# schematic.net
KiCad netlist of a schematic drawn in EasyEDA
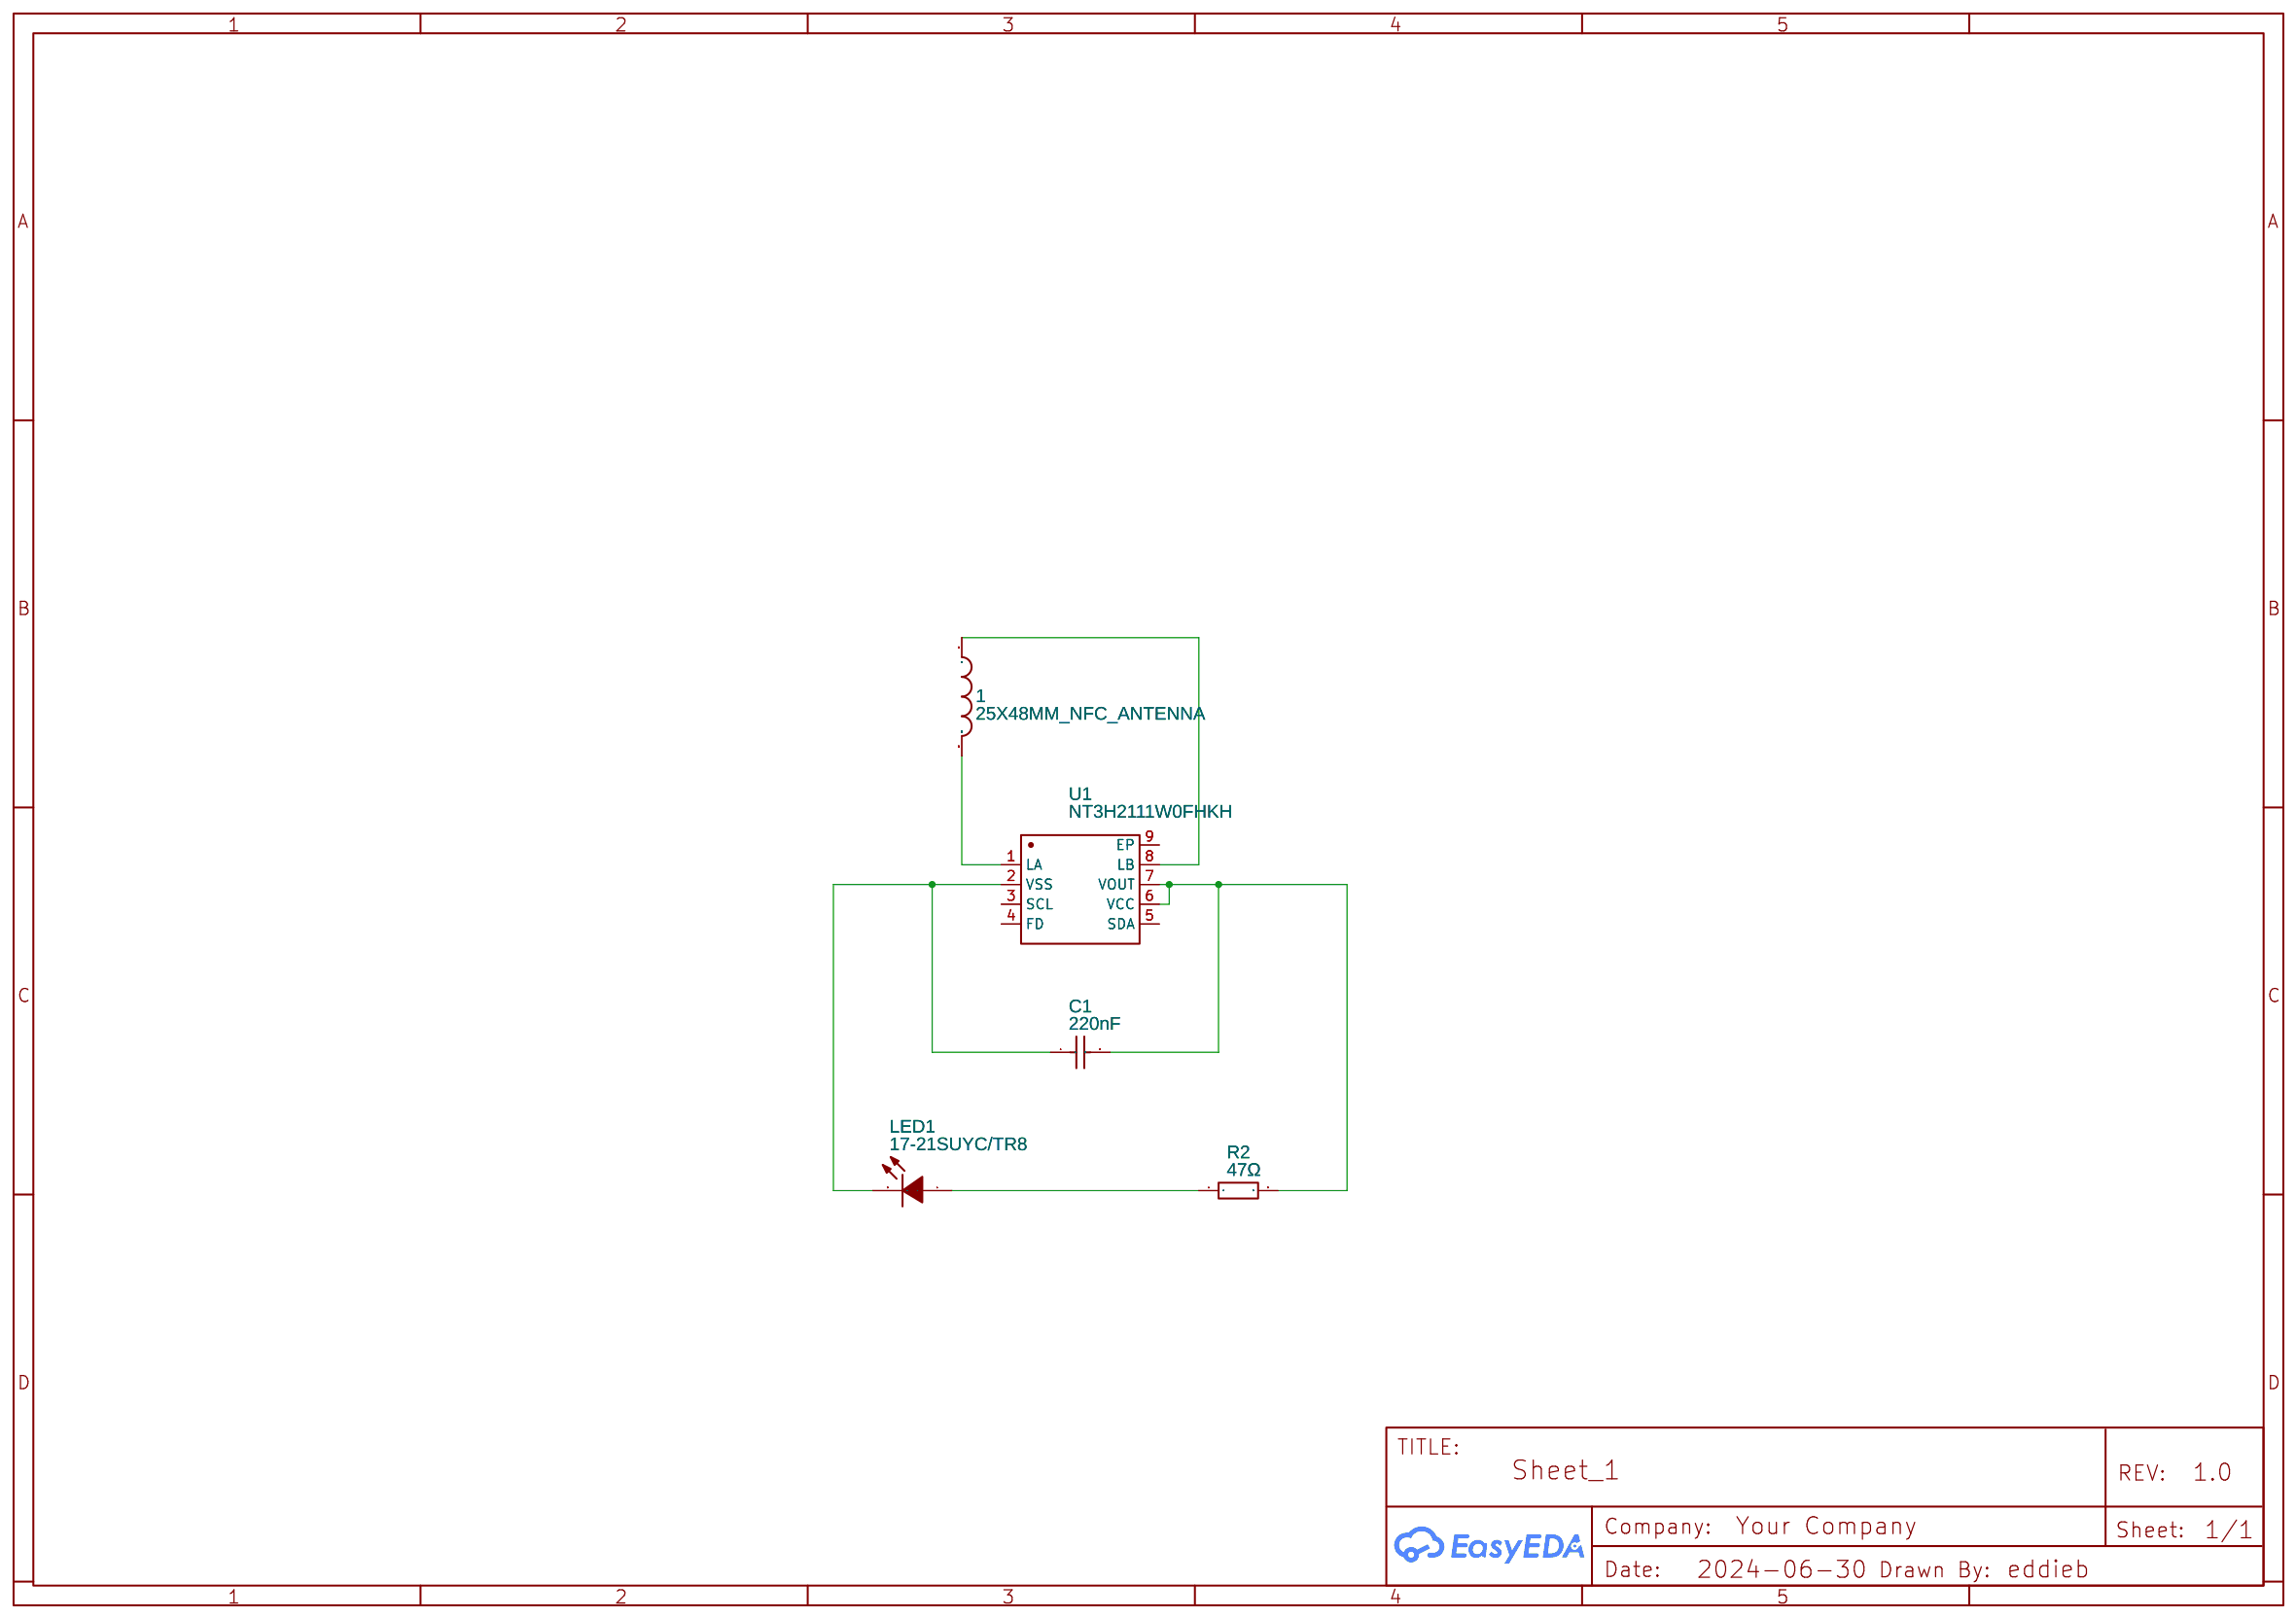
[diagram p0: schematic sheet]

(export (version "E")
  (design (tool "Eeschema 10.0.6"))
  (components
    (comp (ref "1") (value "25X48MM_NFC_ANTENNA") (libsource (lib "") (part "25X48MM_NFC_ANTENNA")))
    (comp (ref "C1")
      (value "220nF")
      (fields
        (field (name "Manufacturer Part") "CL10B224KA8NNNC")
        (field (name "Manufacturer") "SAMSUNG(三星)")
      )
      (libsource (lib "") (part "CL10B224KA8NNNC"))
    )
    (comp (ref "LED1")
      (value "17-21SUYC/TR8")
      (fields (field (name "Manufacturer Part") "KT-0805黄灯") (field (name "Manufacturer") "KENTO"))
      (libsource (lib "") (part "17-21SUYC/TR8"))
    )
    (comp (ref "R2")
      (value "47Ω")
      (fields
        (field (name "Manufacturer Part") "0603WAF470JT5E")
        (field (name "Manufacturer") "UNI-ROYAL(厚声)")
      )
      (libsource (lib "") (part "0603WAF470JT5E"))
    )
    (comp (ref "U1")
      (value "NT3H2111W0FHKH")
      (fields (field (name "Manufacturer") "NXP(恩智浦)"))
      (libsource (lib "") (part "NT3H2111W0FHKH"))
    )
  )
  (nets
    (net (code "1") (name "Net-(LED1-+)") (class "Default")
      (node (ref "LED1") (pin "1") (pinfunction "+_1") (pintype "unspecified"))
      (node (ref "R2") (pin "1") (pinfunction "1_1") (pintype "input"))
    )
    (net (code "2") (name "Net-(LED1--)") (class "Default")
      (node (ref "C1") (pin "1") (pinfunction "1_1") (pintype "input"))
      (node (ref "LED1") (pin "2") (pinfunction "-_2") (pintype "unspecified"))
      (node (ref "U1") (pin "2") (pinfunction "VSS_2") (pintype "unspecified"))
    )
    (net (code "3") (name "Net-(U1-LA)") (class "Default")
      (node (ref "1") (pin "P$2") (pinfunction "P$2_P$2") (pintype "bidirectional"))
      (node (ref "U1") (pin "1") (pinfunction "LA_1") (pintype "unspecified"))
    )
    (net (code "4") (name "Net-(U1-LB)") (class "Default")
      (node (ref "1") (pin "P$1") (pinfunction "P$1_P$1") (pintype "bidirectional"))
      (node (ref "U1") (pin "8") (pinfunction "LB_8") (pintype "unspecified"))
    )
    (net (code "5") (name "Net-(U1-VCC)") (class "Default")
      (node (ref "C1") (pin "2") (pinfunction "2_2") (pintype "input"))
      (node (ref "R2") (pin "2") (pinfunction "2_2") (pintype "input"))
      (node (ref "U1") (pin "6") (pinfunction "VCC_6") (pintype "unspecified"))
      (node (ref "U1") (pin "7") (pinfunction "VOUT_7") (pintype "unspecified"))
    )
    (net (code "6") (name "unconnected-(U1-EP-Pad9)") (class "Default")
      (node (ref "U1") (pin "9") (pinfunction "EP_9") (pintype "unspecified"))
    )
    (net (code "7") (name "unconnected-(U1-FD-Pad4)") (class "Default")
      (node (ref "U1") (pin "4") (pinfunction "FD_4") (pintype "unspecified"))
    )
    (net (code "8") (name "unconnected-(U1-SCL-Pad3)") (class "Default")
      (node (ref "U1") (pin "3") (pinfunction "SCL_3") (pintype "unspecified"))
    )
    (net (code "9") (name "unconnected-(U1-SDA-Pad5)") (class "Default")
      (node (ref "U1") (pin "5") (pinfunction "SDA_5") (pintype "unspecified"))
    )
  )
)
